# UTJ.net
KiCad netlist of a schematic drawn in EAGLE
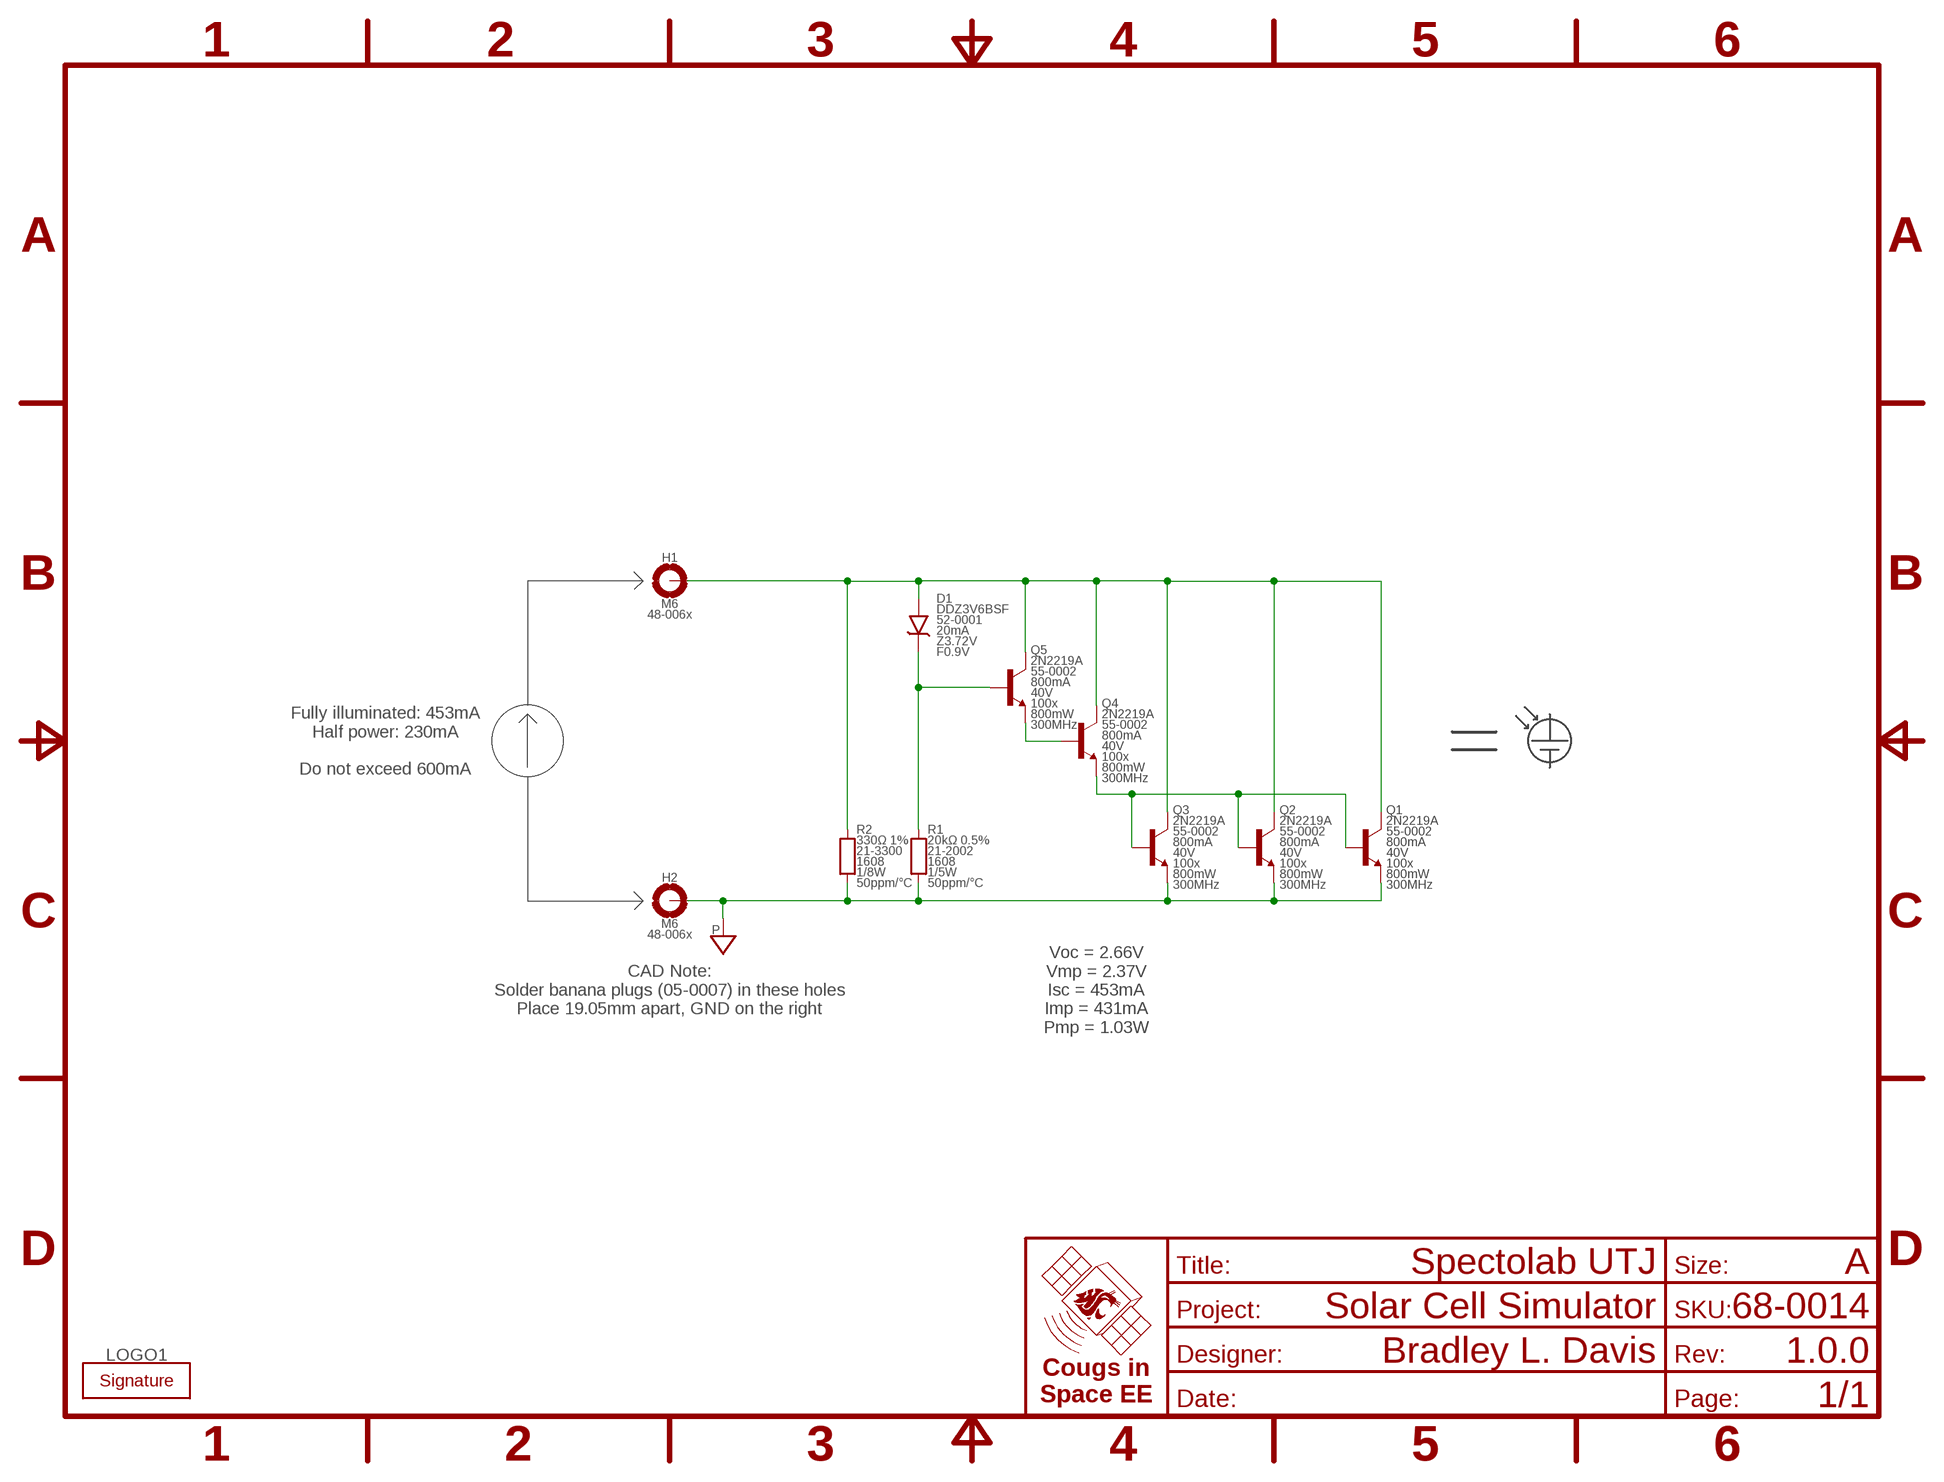
[diagram p0: schematic, sheet 1]

(export (version "E")
  (design (tool "Eeschema 10.0.6"))
  (components
    (comp (ref "D1")
      (value "DDZ3V6BSF")
      (footprint "eagle-import:SOD323F")
      (fields
        (field (name "CURRENT") "20mA")
        (field (name "SKU") "52-0001")
        (field (name "VF") "F0.9V")
        (field (name "VZ") "Z3.72V")
      )
      (libsource (lib "eagle-import") (part "DIODE-ZENER-V-SOD323F-DDZ3V6BSF"))
    )
    (comp (ref "H1")
      (value "M6")
      (footprint "eagle-import:MOUNTING_HOLE-6.6")
      (fields (field (name "SKU") "48-006x"))
      (libsource (lib "eagle-import") (part "MOUNTING_HOLE-6.6"))
    )
    (comp (ref "H2")
      (value "M6")
      (footprint "eagle-import:MOUNTING_HOLE-6.6")
      (fields (field (name "SKU") "48-006x"))
      (libsource (lib "eagle-import") (part "MOUNTING_HOLE-6.6"))
    )
    (comp (ref "LOGO1")
      (value "SIGNATUREBRADLEY")
      (footprint "eagle-import:SIGN-BRADLEY")
      (libsource (lib "eagle-import") (part "SIGNATUREBRADLEY"))
    )
    (comp (ref "Q1")
      (value "2N2219A")
      (footprint "eagle-import:TO-39")
      (fields
        (field (name "FREQ") "300MHz")
        (field (name "GAIN") "100x")
        (field (name "IMAX") "800mA")
        (field (name "POWER") "800mW")
        (field (name "SKU") "55-0002")
        (field (name "VMAX") "40V")
      )
      (libsource (lib "eagle-import") (part "BJT-NPN-TO-39-2N2219A"))
    )
    (comp (ref "Q2")
      (value "2N2219A")
      (footprint "eagle-import:TO-39")
      (fields
        (field (name "FREQ") "300MHz")
        (field (name "GAIN") "100x")
        (field (name "IMAX") "800mA")
        (field (name "POWER") "800mW")
        (field (name "SKU") "55-0002")
        (field (name "VMAX") "40V")
      )
      (libsource (lib "eagle-import") (part "BJT-NPN-TO-39-2N2219A"))
    )
    (comp (ref "Q3")
      (value "2N2219A")
      (footprint "eagle-import:TO-39")
      (fields
        (field (name "FREQ") "300MHz")
        (field (name "GAIN") "100x")
        (field (name "IMAX") "800mA")
        (field (name "POWER") "800mW")
        (field (name "SKU") "55-0002")
        (field (name "VMAX") "40V")
      )
      (libsource (lib "eagle-import") (part "BJT-NPN-TO-39-2N2219A"))
    )
    (comp (ref "Q4")
      (value "2N2219A")
      (footprint "eagle-import:TO-39")
      (fields
        (field (name "FREQ") "300MHz")
        (field (name "GAIN") "100x")
        (field (name "IMAX") "800mA")
        (field (name "POWER") "800mW")
        (field (name "SKU") "55-0002")
        (field (name "VMAX") "40V")
      )
      (libsource (lib "eagle-import") (part "BJT-NPN-TO-39-2N2219A"))
    )
    (comp (ref "Q5")
      (value "2N2219A")
      (footprint "eagle-import:TO-39")
      (fields
        (field (name "FREQ") "300MHz")
        (field (name "GAIN") "100x")
        (field (name "IMAX") "800mA")
        (field (name "POWER") "800mW")
        (field (name "SKU") "55-0002")
        (field (name "VMAX") "40V")
      )
      (libsource (lib "eagle-import") (part "BJT-NPN-TO-39-2N2219A"))
    )
    (comp (ref "R1")
      (value "20kΩ 0.5%")
      (footprint "eagle-import:1608")
      (fields
        (field (name "PACKAGE") "1608")
        (field (name "POWER") "1/5W")
        (field (name "SKU") "21-2002")
        (field (name "TEMP") "50ppm/°C")
      )
      (libsource (lib "eagle-import") (part "RES-V-1608-20K"))
    )
    (comp (ref "R2")
      (value "330Ω 1%")
      (footprint "eagle-import:1608")
      (fields
        (field (name "PACKAGE") "1608")
        (field (name "POWER") "1/8W")
        (field (name "SKU") "21-3300")
        (field (name "TEMP") "50ppm/°C")
      )
      (libsource (lib "eagle-import") (part "RES-V-1608-330R"))
    )
  )
  (nets
    (net (code "1") (name "Net-(Q1-B)") (class "Default")
      (node (ref "Q1") (pin "2") (pinfunction "B_2") (pintype "passive"))
      (node (ref "Q2") (pin "2") (pinfunction "B_2") (pintype "passive"))
      (node (ref "Q3") (pin "2") (pinfunction "B_2") (pintype "passive"))
      (node (ref "Q4") (pin "1") (pinfunction "E_1") (pintype "passive"))
    )
    (net (code "2") (name "Net-(Q1-C)") (class "Default")
      (node (ref "D1") (pin "A") (pinfunction "A_A") (pintype "passive"))
      (node (ref "H1") (pin "1") (pinfunction "MOUNT_1") (pintype "passive"))
      (node (ref "H1") (pin "V1") (pinfunction "MOUNT_V1") (pintype "passive"))
      (node (ref "H1") (pin "V10") (pinfunction "MOUNT_V10") (pintype "passive"))
      (node (ref "H1") (pin "V11") (pinfunction "MOUNT_V11") (pintype "passive"))
      (node (ref "H1") (pin "V12") (pinfunction "MOUNT_V12") (pintype "passive"))
      (node (ref "H1") (pin "V13") (pinfunction "MOUNT_V13") (pintype "passive"))
      (node (ref "H1") (pin "V14") (pinfunction "MOUNT_V14") (pintype "passive"))
      (node (ref "H1") (pin "V15") (pinfunction "MOUNT_V15") (pintype "passive"))
      (node (ref "H1") (pin "V16") (pinfunction "MOUNT_V16") (pintype "passive"))
      (node (ref "H1") (pin "V2") (pinfunction "MOUNT_V2") (pintype "passive"))
      (node (ref "H1") (pin "V3") (pinfunction "MOUNT_V3") (pintype "passive"))
      (node (ref "H1") (pin "V4") (pinfunction "MOUNT_V4") (pintype "passive"))
      (node (ref "H1") (pin "V5") (pinfunction "MOUNT_V5") (pintype "passive"))
      (node (ref "H1") (pin "V6") (pinfunction "MOUNT_V6") (pintype "passive"))
      (node (ref "H1") (pin "V7") (pinfunction "MOUNT_V7") (pintype "passive"))
      (node (ref "H1") (pin "V8") (pinfunction "MOUNT_V8") (pintype "passive"))
      (node (ref "H1") (pin "V9") (pinfunction "MOUNT_V9") (pintype "passive"))
      (node (ref "Q1") (pin "3") (pinfunction "C_3") (pintype "passive"))
      (node (ref "Q2") (pin "3") (pinfunction "C_3") (pintype "passive"))
      (node (ref "Q3") (pin "3") (pinfunction "C_3") (pintype "passive"))
      (node (ref "Q4") (pin "3") (pinfunction "C_3") (pintype "passive"))
      (node (ref "Q5") (pin "3") (pinfunction "C_3") (pintype "passive"))
      (node (ref "R2") (pin "2") (pinfunction "2_2") (pintype "passive"))
    )
    (net (code "3") (name "Net-(Q4-B)") (class "Default")
      (node (ref "Q4") (pin "2") (pinfunction "B_2") (pintype "passive"))
      (node (ref "Q5") (pin "1") (pinfunction "E_1") (pintype "passive"))
    )
    (net (code "4") (name "Net-(Q5-B)") (class "Default")
      (node (ref "D1") (pin "C") (pinfunction "C_C") (pintype "passive"))
      (node (ref "Q5") (pin "2") (pinfunction "B_2") (pintype "passive"))
      (node (ref "R1") (pin "2") (pinfunction "2_2") (pintype "passive"))
    )
    (net (code "5") (name "PGND") (class "Default")
      (node (ref "H2") (pin "1") (pinfunction "MOUNT_1") (pintype "passive"))
      (node (ref "H2") (pin "V1") (pinfunction "MOUNT_V1") (pintype "passive"))
      (node (ref "H2") (pin "V10") (pinfunction "MOUNT_V10") (pintype "passive"))
      (node (ref "H2") (pin "V11") (pinfunction "MOUNT_V11") (pintype "passive"))
      (node (ref "H2") (pin "V12") (pinfunction "MOUNT_V12") (pintype "passive"))
      (node (ref "H2") (pin "V13") (pinfunction "MOUNT_V13") (pintype "passive"))
      (node (ref "H2") (pin "V14") (pinfunction "MOUNT_V14") (pintype "passive"))
      (node (ref "H2") (pin "V15") (pinfunction "MOUNT_V15") (pintype "passive"))
      (node (ref "H2") (pin "V16") (pinfunction "MOUNT_V16") (pintype "passive"))
      (node (ref "H2") (pin "V2") (pinfunction "MOUNT_V2") (pintype "passive"))
      (node (ref "H2") (pin "V3") (pinfunction "MOUNT_V3") (pintype "passive"))
      (node (ref "H2") (pin "V4") (pinfunction "MOUNT_V4") (pintype "passive"))
      (node (ref "H2") (pin "V5") (pinfunction "MOUNT_V5") (pintype "passive"))
      (node (ref "H2") (pin "V6") (pinfunction "MOUNT_V6") (pintype "passive"))
      (node (ref "H2") (pin "V7") (pinfunction "MOUNT_V7") (pintype "passive"))
      (node (ref "H2") (pin "V8") (pinfunction "MOUNT_V8") (pintype "passive"))
      (node (ref "H2") (pin "V9") (pinfunction "MOUNT_V9") (pintype "passive"))
      (node (ref "Q1") (pin "1") (pinfunction "E_1") (pintype "passive"))
      (node (ref "Q2") (pin "1") (pinfunction "E_1") (pintype "passive"))
      (node (ref "Q3") (pin "1") (pinfunction "E_1") (pintype "passive"))
      (node (ref "R1") (pin "1") (pinfunction "1_1") (pintype "passive"))
      (node (ref "R2") (pin "1") (pinfunction "1_1") (pintype "passive"))
    )
  )
)
